# ar488_driver_schematic.net
KiCad netlist of a schematic drawn in Altium Designer
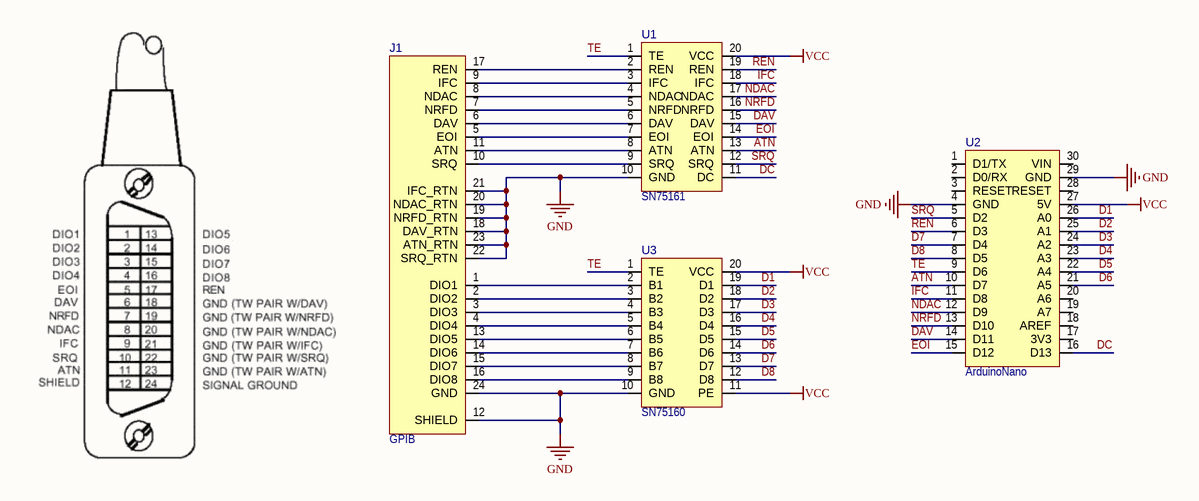
[diagram p0: ar488_driver_schematic.SchDoc]

(export (version "E")
  (design (tool "Eeschema 10.0.6"))
  (components
    (comp (ref "J1")
      (value "GPIB")
      (footprint "GPIB")
      (description "Wire-to-Board GPIB Connections")
      (libsource (lib "ar488_driver_schematic_library") (part "GPIB"))
    )
    (comp (ref "U1")
      (value "SN75161")
      (footprint "SN75161")
      (description "Octal General-Purpose Interface Bus Tranceiver")
      (libsource (lib "ar488_driver_schematic_library") (part "SN75161"))
    )
    (comp (ref "U2")
      (value "ArduinoNano")
      (footprint "NANO")
      (description "Arduino Nano")
      (libsource (lib "ar488_driver_schematic_library") (part "ArduinoNano"))
    )
    (comp (ref "U3")
      (value "SN75160")
      (footprint "SN75160")
      (description "Octal General-Purpose Interface Bus Tranceiver")
      (libsource (lib "ar488_driver_schematic_library") (part "SN75160"))
    )
  )
  (nets
    (net (code "1") (name "/ATN") (class "Default")
      (node (ref "U1") (pin "13") (pinfunction "ATN_13") (pintype "passive"))
      (node (ref "U2") (pin "10") (pinfunction "D7_10") (pintype "passive"))
    )
    (net (code "2") (name "/D1") (class "Default")
      (node (ref "U2") (pin "26") (pinfunction "A0_26") (pintype "passive"))
      (node (ref "U3") (pin "19") (pinfunction "D1_19") (pintype "passive"))
    )
    (net (code "3") (name "/D2") (class "Default")
      (node (ref "U2") (pin "25") (pinfunction "A1_25") (pintype "passive"))
      (node (ref "U3") (pin "18") (pinfunction "D2_18") (pintype "passive"))
    )
    (net (code "4") (name "/D3") (class "Default")
      (node (ref "U2") (pin "24") (pinfunction "A2_24") (pintype "passive"))
      (node (ref "U3") (pin "17") (pinfunction "D3_17") (pintype "passive"))
    )
    (net (code "5") (name "/D4") (class "Default")
      (node (ref "U2") (pin "23") (pinfunction "A3_23") (pintype "passive"))
      (node (ref "U3") (pin "16") (pinfunction "D4_16") (pintype "passive"))
    )
    (net (code "6") (name "/D5") (class "Default")
      (node (ref "U2") (pin "22") (pinfunction "A4_22") (pintype "passive"))
      (node (ref "U3") (pin "15") (pinfunction "D5_15") (pintype "passive"))
    )
    (net (code "7") (name "/D6") (class "Default")
      (node (ref "U2") (pin "21") (pinfunction "A5_21") (pintype "passive"))
      (node (ref "U3") (pin "14") (pinfunction "D6_14") (pintype "passive"))
    )
    (net (code "8") (name "/D7") (class "Default")
      (node (ref "U2") (pin "7") (pinfunction "D4_7") (pintype "passive"))
      (node (ref "U3") (pin "13") (pinfunction "D7_13") (pintype "passive"))
    )
    (net (code "9") (name "/D8") (class "Default")
      (node (ref "U2") (pin "8") (pinfunction "D5_8") (pintype "passive"))
      (node (ref "U3") (pin "12") (pinfunction "D8_12") (pintype "passive"))
    )
    (net (code "10") (name "/DAV") (class "Default")
      (node (ref "U1") (pin "15") (pinfunction "DAV_15") (pintype "passive"))
      (node (ref "U2") (pin "14") (pinfunction "D11_14") (pintype "passive"))
    )
    (net (code "11") (name "/DC") (class "Default")
      (node (ref "U1") (pin "11") (pinfunction "DC_11") (pintype "passive"))
      (node (ref "U2") (pin "16") (pinfunction "D13_16") (pintype "passive"))
    )
    (net (code "12") (name "/EOI") (class "Default")
      (node (ref "U1") (pin "14") (pinfunction "EOI_14") (pintype "passive"))
      (node (ref "U2") (pin "15") (pinfunction "D12_15") (pintype "passive"))
    )
    (net (code "13") (name "/IFC") (class "Default")
      (node (ref "U1") (pin "18") (pinfunction "IFC_18") (pintype "passive"))
      (node (ref "U2") (pin "11") (pinfunction "D8_11") (pintype "passive"))
    )
    (net (code "14") (name "/NDAC") (class "Default")
      (node (ref "U1") (pin "17") (pinfunction "NDAC_17") (pintype "passive"))
      (node (ref "U2") (pin "12") (pinfunction "D9_12") (pintype "passive"))
    )
    (net (code "15") (name "/NRFD") (class "Default")
      (node (ref "U1") (pin "16") (pinfunction "NRFD_16") (pintype "passive"))
      (node (ref "U2") (pin "13") (pinfunction "D10_13") (pintype "passive"))
    )
    (net (code "16") (name "/REN") (class "Default")
      (node (ref "U1") (pin "19") (pinfunction "REN_19") (pintype "passive"))
      (node (ref "U2") (pin "6") (pinfunction "D3_6") (pintype "passive"))
    )
    (net (code "17") (name "/SRQ") (class "Default")
      (node (ref "U1") (pin "12") (pinfunction "SRQ_12") (pintype "passive"))
      (node (ref "U2") (pin "5") (pinfunction "D2_5") (pintype "passive"))
    )
    (net (code "18") (name "/TE") (class "Default")
      (node (ref "U1") (pin "1") (pinfunction "TE_1") (pintype "passive"))
      (node (ref "U2") (pin "9") (pinfunction "D6_9") (pintype "passive"))
      (node (ref "U3") (pin "1") (pinfunction "TE_1") (pintype "passive"))
    )
    (net (code "19") (name "GND") (class "Default")
      (node (ref "J1") (pin "12") (pinfunction "SHIELD_12") (pintype "passive"))
      (node (ref "J1") (pin "18") (pinfunction "DAV_RTN_18") (pintype "passive"))
      (node (ref "J1") (pin "19") (pinfunction "NRFD_RTN_19") (pintype "passive"))
      (node (ref "J1") (pin "20") (pinfunction "NDAC_RTN_20") (pintype "passive"))
      (node (ref "J1") (pin "21") (pinfunction "IFC_RTN_21") (pintype "passive"))
      (node (ref "J1") (pin "22") (pinfunction "SRQ_RTN_22") (pintype "passive"))
      (node (ref "J1") (pin "23") (pinfunction "ATN_RTN_23") (pintype "passive"))
      (node (ref "J1") (pin "24") (pinfunction "GND_24") (pintype "passive"))
      (node (ref "U1") (pin "10") (pinfunction "GND_10") (pintype "passive"))
      (node (ref "U2") (pin "29") (pinfunction "GND_29") (pintype "passive"))
      (node (ref "U2") (pin "4") (pinfunction "GND_4") (pintype "passive"))
      (node (ref "U3") (pin "10") (pinfunction "GND_10") (pintype "passive"))
    )
    (net (code "20") (name "Net-(J1-ATN)") (class "Default")
      (node (ref "J1") (pin "11") (pinfunction "ATN_11") (pintype "passive"))
      (node (ref "U1") (pin "8") (pinfunction "ATN_8") (pintype "passive"))
    )
    (net (code "21") (name "Net-(J1-DAV)") (class "Default")
      (node (ref "J1") (pin "6") (pinfunction "DAV_6") (pintype "passive"))
      (node (ref "U1") (pin "6") (pinfunction "DAV_6") (pintype "passive"))
    )
    (net (code "22") (name "Net-(J1-DIO1)") (class "Default")
      (node (ref "J1") (pin "1") (pinfunction "DIO1_1") (pintype "passive"))
      (node (ref "U3") (pin "2") (pinfunction "B1_2") (pintype "passive"))
    )
    (net (code "23") (name "Net-(J1-DIO2)") (class "Default")
      (node (ref "J1") (pin "2") (pinfunction "DIO2_2") (pintype "passive"))
      (node (ref "U3") (pin "3") (pinfunction "B2_3") (pintype "passive"))
    )
    (net (code "24") (name "Net-(J1-DIO3)") (class "Default")
      (node (ref "J1") (pin "3") (pinfunction "DIO3_3") (pintype "passive"))
      (node (ref "U3") (pin "4") (pinfunction "B3_4") (pintype "passive"))
    )
    (net (code "25") (name "Net-(J1-DIO4)") (class "Default")
      (node (ref "J1") (pin "4") (pinfunction "DIO4_4") (pintype "passive"))
      (node (ref "U3") (pin "5") (pinfunction "B4_5") (pintype "passive"))
    )
    (net (code "26") (name "Net-(J1-DIO5)") (class "Default")
      (node (ref "J1") (pin "13") (pinfunction "DIO5_13") (pintype "passive"))
      (node (ref "U3") (pin "6") (pinfunction "B5_6") (pintype "passive"))
    )
    (net (code "27") (name "Net-(J1-DIO6)") (class "Default")
      (node (ref "J1") (pin "14") (pinfunction "DIO6_14") (pintype "passive"))
      (node (ref "U3") (pin "7") (pinfunction "B6_7") (pintype "passive"))
    )
    (net (code "28") (name "Net-(J1-DIO7)") (class "Default")
      (node (ref "J1") (pin "15") (pinfunction "DIO7_15") (pintype "passive"))
      (node (ref "U3") (pin "8") (pinfunction "B7_8") (pintype "passive"))
    )
    (net (code "29") (name "Net-(J1-DIO8)") (class "Default")
      (node (ref "J1") (pin "16") (pinfunction "DIO8_16") (pintype "passive"))
      (node (ref "U3") (pin "9") (pinfunction "B8_9") (pintype "passive"))
    )
    (net (code "30") (name "Net-(J1-EOI)") (class "Default")
      (node (ref "J1") (pin "5") (pinfunction "EOI_5") (pintype "passive"))
      (node (ref "U1") (pin "7") (pinfunction "EOI_7") (pintype "passive"))
    )
    (net (code "31") (name "Net-(J1-IFC)") (class "Default")
      (node (ref "J1") (pin "9") (pinfunction "IFC_9") (pintype "passive"))
      (node (ref "U1") (pin "3") (pinfunction "IFC_3") (pintype "passive"))
    )
    (net (code "32") (name "Net-(J1-NDAC)") (class "Default")
      (node (ref "J1") (pin "8") (pinfunction "NDAC_8") (pintype "passive"))
      (node (ref "U1") (pin "4") (pinfunction "NDAC_4") (pintype "passive"))
    )
    (net (code "33") (name "Net-(J1-NRFD)") (class "Default")
      (node (ref "J1") (pin "7") (pinfunction "NRFD_7") (pintype "passive"))
      (node (ref "U1") (pin "5") (pinfunction "NRFD_5") (pintype "passive"))
    )
    (net (code "34") (name "Net-(J1-REN)") (class "Default")
      (node (ref "J1") (pin "17") (pinfunction "REN_17") (pintype "passive"))
      (node (ref "U1") (pin "2") (pinfunction "REN_2") (pintype "passive"))
    )
    (net (code "35") (name "Net-(J1-SRQ)") (class "Default")
      (node (ref "J1") (pin "10") (pinfunction "SRQ_10") (pintype "passive"))
      (node (ref "U1") (pin "9") (pinfunction "SRQ_9") (pintype "passive"))
    )
    (net (code "36") (name "VCC") (class "Default")
      (node (ref "U1") (pin "20") (pinfunction "VCC_20") (pintype "passive"))
      (node (ref "U2") (pin "27") (pinfunction "5V_27") (pintype "passive"))
      (node (ref "U3") (pin "11") (pinfunction "PE_11") (pintype "passive"))
      (node (ref "U3") (pin "20") (pinfunction "VCC_20") (pintype "passive"))
    )
    (net (code "37") (name "unconnected-(U2-3V3-Pad17)") (class "Default")
      (node (ref "U2") (pin "17") (pinfunction "3V3_17") (pintype "passive"))
    )
    (net (code "38") (name "unconnected-(U2-A6-Pad20)") (class "Default")
      (node (ref "U2") (pin "20") (pinfunction "A6_20") (pintype "passive"))
    )
    (net (code "39") (name "unconnected-(U2-A7-Pad19)") (class "Default")
      (node (ref "U2") (pin "19") (pinfunction "A7_19") (pintype "passive"))
    )
    (net (code "40") (name "unconnected-(U2-AREF-Pad18)") (class "Default")
      (node (ref "U2") (pin "18") (pinfunction "AREF_18") (pintype "passive"))
    )
    (net (code "41") (name "unconnected-(U2-D0{slash}RX-Pad2)") (class "Default")
      (node (ref "U2") (pin "2") (pinfunction "D0/RX_2") (pintype "passive"))
    )
    (net (code "42") (name "unconnected-(U2-D1{slash}TX-Pad1)") (class "Default")
      (node (ref "U2") (pin "1") (pinfunction "D1/TX_1") (pintype "passive"))
    )
    (net (code "43") (name "unconnected-(U2-RESET-Pad3)") (class "Default")
      (node (ref "U2") (pin "3") (pinfunction "RESET_3") (pintype "passive"))
    )
    (net (code "44") (name "unconnected-(U2-RESET-Pad28)") (class "Default")
      (node (ref "U2") (pin "28") (pinfunction "RESET_28") (pintype "passive"))
    )
    (net (code "45") (name "unconnected-(U2-VIN-Pad30)") (class "Default")
      (node (ref "U2") (pin "30") (pinfunction "VIN_30") (pintype "passive"))
    )
  )
)
